# A7_FUNCTION2_-.net
KiCad netlist of a schematic drawn in Altium Designer
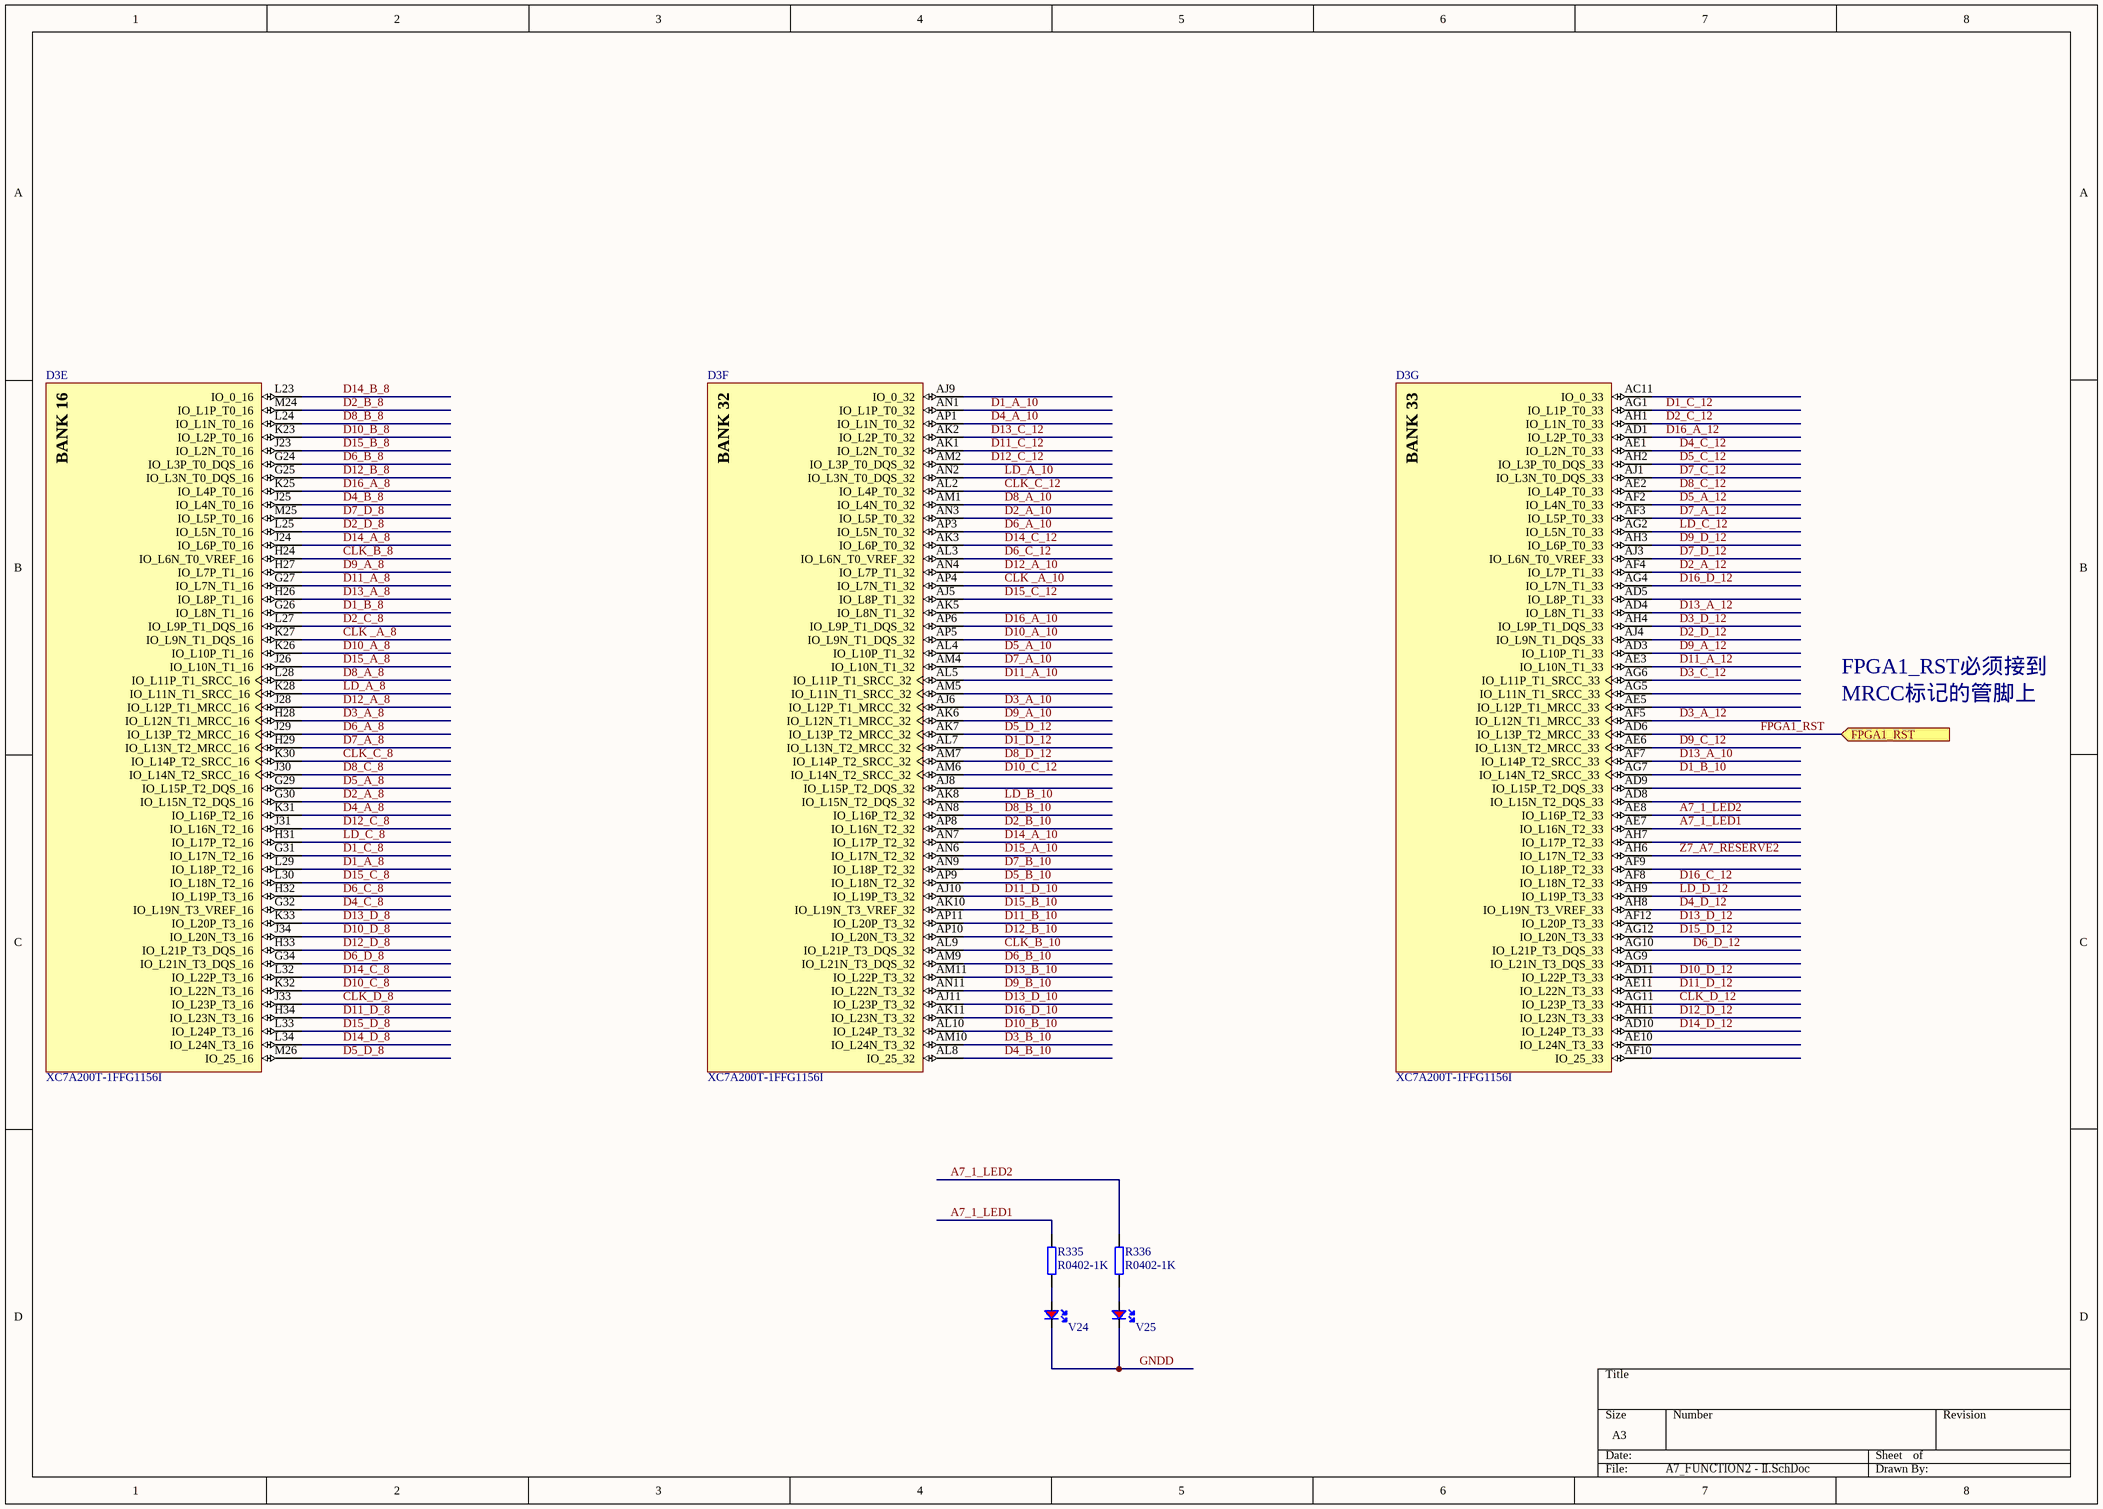
[diagram p0: A7_FUNCTION2 - Ⅱ.SchDoc]

(export (version "E")
  (design (tool "Eeschema 10.0.6"))
  (components
    (comp (ref "D3")
      (value "XC7A200T-1FFG1156I")
      (footprint "FFG1156")
      (description "Artix-7 FPGA, 500 User I/Os, 16 GTP, 1156-Ball BGA, Speed Grade 1, Industrial Grade, Pb-Free")
      (fields (field (name "GENERIC PART NUMBER") "XC7A200T") (field (name "MANUFACTURER") "Xilinx"))
      (libsource (lib "Xilinx Artix-7") (part "XC7A200T-1FFG1156I"))
    )
    (comp (ref "R335")
      (value "R0402-1K")
      (footprint "R0402")
      (fields (field (name "SCHEMATIC_PART") "RES") (field (name "MANUFACTURER") "SAMSUNG"))
      (libsource (lib "Database_Libs1") (part "RES"))
    )
    (comp (ref "R336")
      (value "R0402-1K")
      (footprint "R0402")
      (fields (field (name "SCHEMATIC_PART") "RES") (field (name "MANUFACTURER") "SAMSUNG"))
      (libsource (lib "Database_Libs1") (part "RES"))
    )
    (comp (ref "V24")
      (value "LED-R0603")
      (footprint "LED-R0603")
      (description "表贴发光二极管, 0603封装, 体积1.6x0.8mm, 红色, 高度0.8mm")
      (fields (field (name "SCHEMATIC_PART") "LED-R"))
      (libsource (lib "Database_Libs1") (part "LED-R"))
    )
    (comp (ref "V25")
      (value "LED-R0603")
      (footprint "LED-R0603")
      (description "表贴发光二极管, 0603封装, 体积1.6x0.8mm, 红色, 高度0.8mm")
      (fields (field (name "SCHEMATIC_PART") "LED-R"))
      (libsource (lib "Database_Libs1") (part "LED-R"))
    )
  )
  (nets
    (net (code "1") (name "/A7_1_LED1") (class "Default")
      (node (ref "D3") (pin "AE7") (pinfunction "IO_L16N_T2_33_AE7") (pintype "bidirectional"))
      (node (ref "R335") (pin "2") (pintype "passive"))
    )
    (net (code "2") (name "/A7_1_LED2") (class "Default")
      (node (ref "D3") (pin "AE8") (pinfunction "IO_L16P_T2_33_AE8") (pintype "bidirectional"))
      (node (ref "R336") (pin "2") (pintype "passive"))
    )
    (net (code "3") (name "/CLK _A_8") (class "Default")
      (node (ref "D3") (pin "K27") (pinfunction "IO_L9N_T1_DQS_16_K27") (pintype "bidirectional"))
    )
    (net (code "4") (name "/CLK _A_10") (class "Default")
      (node (ref "D3") (pin "AP4") (pinfunction "IO_L7N_T1_32_AP4") (pintype "bidirectional"))
    )
    (net (code "5") (name "/CLK_B_8") (class "Default")
      (node (ref "D3") (pin "H24") (pinfunction "IO_L6N_T0_VREF_16_H24") (pintype "bidirectional"))
    )
    (net (code "6") (name "/CLK_B_10") (class "Default")
      (node (ref "D3") (pin "AL9") (pinfunction "IO_L21P_T3_DQS_32_AL9") (pintype "bidirectional"))
    )
    (net (code "7") (name "/CLK_C_8") (class "Default")
      (node (ref "D3") (pin "K30") (pinfunction "IO_L14P_T2_SRCC_16_K30") (pintype "bidirectional"))
    )
    (net (code "8") (name "/CLK_C_12") (class "Default")
      (node (ref "D3") (pin "AL2") (pinfunction "IO_L4P_T0_32_AL2") (pintype "bidirectional"))
    )
    (net (code "9") (name "/CLK_D_8") (class "Default")
      (node (ref "D3") (pin "J33") (pinfunction "IO_L23P_T3_16_J33") (pintype "bidirectional"))
    )
    (net (code "10") (name "/CLK_D_12") (class "Default")
      (node (ref "D3") (pin "AG11") (pinfunction "IO_L23P_T3_33_AG11") (pintype "bidirectional"))
    )
    (net (code "11") (name "/D1_A_8") (class "Default")
      (node (ref "D3") (pin "L29") (pinfunction "IO_L18P_T2_16_L29") (pintype "bidirectional"))
    )
    (net (code "12") (name "/D1_A_10") (class "Default")
      (node (ref "D3") (pin "AN1") (pinfunction "IO_L1P_T0_32_AN1") (pintype "bidirectional"))
    )
    (net (code "13") (name "/D1_B_8") (class "Default")
      (node (ref "D3") (pin "G26") (pinfunction "IO_L8N_T1_16_G26") (pintype "bidirectional"))
    )
    (net (code "14") (name "/D1_B_10") (class "Default")
      (node (ref "D3") (pin "AG7") (pinfunction "IO_L14N_T2_SRCC_33_AG7") (pintype "bidirectional"))
    )
    (net (code "15") (name "/D1_C_8") (class "Default")
      (node (ref "D3") (pin "G31") (pinfunction "IO_L17N_T2_16_G31") (pintype "bidirectional"))
    )
    (net (code "16") (name "/D1_C_12") (class "Default")
      (node (ref "D3") (pin "AG1") (pinfunction "IO_L1P_T0_33_AG1") (pintype "bidirectional"))
    )
    (net (code "17") (name "/D1_D_12") (class "Default")
      (node (ref "D3") (pin "AL7") (pinfunction "IO_L13N_T2_MRCC_32_AL7") (pintype "bidirectional"))
    )
    (net (code "18") (name "/D2_A_8") (class "Default")
      (node (ref "D3") (pin "G30") (pinfunction "IO_L15N_T2_DQS_16_G30") (pintype "bidirectional"))
    )
    (net (code "19") (name "/D2_A_10") (class "Default")
      (node (ref "D3") (pin "AN3") (pinfunction "IO_L5P_T0_32_AN3") (pintype "bidirectional"))
    )
    (net (code "20") (name "/D2_A_12") (class "Default")
      (node (ref "D3") (pin "AF4") (pinfunction "IO_L7P_T1_33_AF4") (pintype "bidirectional"))
    )
    (net (code "21") (name "/D2_B_8") (class "Default")
      (node (ref "D3") (pin "M24") (pinfunction "IO_L1P_T0_16_M24") (pintype "bidirectional"))
    )
    (net (code "22") (name "/D2_B_10") (class "Default")
      (node (ref "D3") (pin "AP8") (pinfunction "IO_L16N_T2_32_AP8") (pintype "bidirectional"))
    )
    (net (code "23") (name "/D2_C_8") (class "Default")
      (node (ref "D3") (pin "L27") (pinfunction "IO_L9P_T1_DQS_16_L27") (pintype "bidirectional"))
    )
    (net (code "24") (name "/D2_C_12") (class "Default")
      (node (ref "D3") (pin "AH1") (pinfunction "IO_L1N_T0_33_AH1") (pintype "bidirectional"))
    )
    (net (code "25") (name "/D2_D_8") (class "Default")
      (node (ref "D3") (pin "L25") (pinfunction "IO_L5N_T0_16_L25") (pintype "bidirectional"))
    )
    (net (code "26") (name "/D2_D_12") (class "Default")
      (node (ref "D3") (pin "AJ4") (pinfunction "IO_L9N_T1_DQS_33_AJ4") (pintype "bidirectional"))
    )
    (net (code "27") (name "/D3_A_8") (class "Default")
      (node (ref "D3") (pin "H28") (pinfunction "IO_L12N_T1_MRCC_16_H28") (pintype "bidirectional"))
    )
    (net (code "28") (name "/D3_A_10") (class "Default")
      (node (ref "D3") (pin "AJ6") (pinfunction "IO_L12P_T1_MRCC_32_AJ6") (pintype "bidirectional"))
    )
    (net (code "29") (name "/D3_A_12") (class "Default")
      (node (ref "D3") (pin "AF5") (pinfunction "IO_L12N_T1_MRCC_33_AF5") (pintype "bidirectional"))
    )
    (net (code "30") (name "/D3_B_10") (class "Default")
      (node (ref "D3") (pin "AM10") (pinfunction "IO_L24N_T3_32_AM10") (pintype "bidirectional"))
    )
    (net (code "31") (name "/D3_C_12") (class "Default")
      (node (ref "D3") (pin "AG6") (pinfunction "IO_L11P_T1_SRCC_33_AG6") (pintype "bidirectional"))
    )
    (net (code "32") (name "/D3_D_12") (class "Default")
      (node (ref "D3") (pin "AH4") (pinfunction "IO_L9P_T1_DQS_33_AH4") (pintype "bidirectional"))
    )
    (net (code "33") (name "/D4_A_8") (class "Default")
      (node (ref "D3") (pin "K31") (pinfunction "IO_L16P_T2_16_K31") (pintype "bidirectional"))
    )
    (net (code "34") (name "/D4_A_10") (class "Default")
      (node (ref "D3") (pin "AP1") (pinfunction "IO_L1N_T0_32_AP1") (pintype "bidirectional"))
    )
    (net (code "35") (name "/D4_B_8") (class "Default")
      (node (ref "D3") (pin "J25") (pinfunction "IO_L4N_T0_16_J25") (pintype "bidirectional"))
    )
    (net (code "36") (name "/D4_B_10") (class "Default")
      (node (ref "D3") (pin "AL8") (pinfunction "IO_25_32_AL8") (pintype "bidirectional"))
    )
    (net (code "37") (name "/D4_C_8") (class "Default")
      (node (ref "D3") (pin "G32") (pinfunction "IO_L19N_T3_VREF_16_G32") (pintype "bidirectional"))
    )
    (net (code "38") (name "/D4_C_12") (class "Default")
      (node (ref "D3") (pin "AE1") (pinfunction "IO_L2N_T0_33_AE1") (pintype "bidirectional"))
    )
    (net (code "39") (name "/D4_D_12") (class "Default")
      (node (ref "D3") (pin "AH8") (pinfunction "IO_L19N_T3_VREF_33_AH8") (pintype "bidirectional"))
    )
    (net (code "40") (name "/D5_A_8") (class "Default")
      (node (ref "D3") (pin "G29") (pinfunction "IO_L15P_T2_DQS_16_G29") (pintype "bidirectional"))
    )
    (net (code "41") (name "/D5_A_10") (class "Default")
      (node (ref "D3") (pin "AL4") (pinfunction "IO_L10P_T1_32_AL4") (pintype "bidirectional"))
    )
    (net (code "42") (name "/D5_A_12") (class "Default")
      (node (ref "D3") (pin "AF2") (pinfunction "IO_L4N_T0_33_AF2") (pintype "bidirectional"))
    )
    (net (code "43") (name "/D5_B_10") (class "Default")
      (node (ref "D3") (pin "AP9") (pinfunction "IO_L18N_T2_32_AP9") (pintype "bidirectional"))
    )
    (net (code "44") (name "/D5_C_12") (class "Default")
      (node (ref "D3") (pin "AH2") (pinfunction "IO_L3P_T0_DQS_33_AH2") (pintype "bidirectional"))
    )
    (net (code "45") (name "/D5_D_8") (class "Default")
      (node (ref "D3") (pin "M26") (pinfunction "IO_25_16_M26") (pintype "bidirectional"))
    )
    (net (code "46") (name "/D5_D_12") (class "Default")
      (node (ref "D3") (pin "AK7") (pinfunction "IO_L13P_T2_MRCC_32_AK7") (pintype "bidirectional"))
    )
    (net (code "47") (name "/D6_A_8") (class "Default")
      (node (ref "D3") (pin "J29") (pinfunction "IO_L13P_T2_MRCC_16_J29") (pintype "bidirectional"))
    )
    (net (code "48") (name "/D6_A_10") (class "Default")
      (node (ref "D3") (pin "AP3") (pinfunction "IO_L5N_T0_32_AP3") (pintype "bidirectional"))
    )
    (net (code "49") (name "/D6_B_8") (class "Default")
      (node (ref "D3") (pin "G24") (pinfunction "IO_L3P_T0_DQS_16_G24") (pintype "bidirectional"))
    )
    (net (code "50") (name "/D6_B_10") (class "Default")
      (node (ref "D3") (pin "AM9") (pinfunction "IO_L21N_T3_DQS_32_AM9") (pintype "bidirectional"))
    )
    (net (code "51") (name "/D6_C_8") (class "Default")
      (node (ref "D3") (pin "H32") (pinfunction "IO_L19P_T3_16_H32") (pintype "bidirectional"))
    )
    (net (code "52") (name "/D6_C_12") (class "Default")
      (node (ref "D3") (pin "AL3") (pinfunction "IO_L6N_T0_VREF_32_AL3") (pintype "bidirectional"))
    )
    (net (code "53") (name "/D6_D_8") (class "Default")
      (node (ref "D3") (pin "G34") (pinfunction "IO_L21N_T3_DQS_16_G34") (pintype "bidirectional"))
    )
    (net (code "54") (name "/D6_D_12") (class "Default")
      (node (ref "D3") (pin "AG10") (pinfunction "IO_L21P_T3_DQS_33_AG10") (pintype "bidirectional"))
    )
    (net (code "55") (name "/D7_A_8") (class "Default")
      (node (ref "D3") (pin "H29") (pinfunction "IO_L13N_T2_MRCC_16_H29") (pintype "bidirectional"))
    )
    (net (code "56") (name "/D7_A_10") (class "Default")
      (node (ref "D3") (pin "AM4") (pinfunction "IO_L10N_T1_32_AM4") (pintype "bidirectional"))
    )
    (net (code "57") (name "/D7_A_12") (class "Default")
      (node (ref "D3") (pin "AF3") (pinfunction "IO_L5P_T0_33_AF3") (pintype "bidirectional"))
    )
    (net (code "58") (name "/D7_B_10") (class "Default")
      (node (ref "D3") (pin "AN9") (pinfunction "IO_L18P_T2_32_AN9") (pintype "bidirectional"))
    )
    (net (code "59") (name "/D7_C_12") (class "Default")
      (node (ref "D3") (pin "AJ1") (pinfunction "IO_L3N_T0_DQS_33_AJ1") (pintype "bidirectional"))
    )
    (net (code "60") (name "/D7_D_8") (class "Default")
      (node (ref "D3") (pin "M25") (pinfunction "IO_L5P_T0_16_M25") (pintype "bidirectional"))
    )
    (net (code "61") (name "/D7_D_12") (class "Default")
      (node (ref "D3") (pin "AJ3") (pinfunction "IO_L6N_T0_VREF_33_AJ3") (pintype "bidirectional"))
    )
    (net (code "62") (name "/D8_A_8") (class "Default")
      (node (ref "D3") (pin "L28") (pinfunction "IO_L11P_T1_SRCC_16_L28") (pintype "bidirectional"))
    )
    (net (code "63") (name "/D8_A_10") (class "Default")
      (node (ref "D3") (pin "AM1") (pinfunction "IO_L4N_T0_32_AM1") (pintype "bidirectional"))
    )
    (net (code "64") (name "/D8_B_8") (class "Default")
      (node (ref "D3") (pin "L24") (pinfunction "IO_L1N_T0_16_L24") (pintype "bidirectional"))
    )
    (net (code "65") (name "/D8_B_10") (class "Default")
      (node (ref "D3") (pin "AN8") (pinfunction "IO_L16P_T2_32_AN8") (pintype "bidirectional"))
    )
    (net (code "66") (name "/D8_C_8") (class "Default")
      (node (ref "D3") (pin "J30") (pinfunction "IO_L14N_T2_SRCC_16_J30") (pintype "bidirectional"))
    )
    (net (code "67") (name "/D8_C_12") (class "Default")
      (node (ref "D3") (pin "AE2") (pinfunction "IO_L4P_T0_33_AE2") (pintype "bidirectional"))
    )
    (net (code "68") (name "/D8_D_12") (class "Default")
      (node (ref "D3") (pin "AM7") (pinfunction "IO_L14P_T2_SRCC_32_AM7") (pintype "bidirectional"))
    )
    (net (code "69") (name "/D9_A_8") (class "Default")
      (node (ref "D3") (pin "H27") (pinfunction "IO_L7P_T1_16_H27") (pintype "bidirectional"))
    )
    (net (code "70") (name "/D9_A_10") (class "Default")
      (node (ref "D3") (pin "AK6") (pinfunction "IO_L12N_T1_MRCC_32_AK6") (pintype "bidirectional"))
    )
    (net (code "71") (name "/D9_A_12") (class "Default")
      (node (ref "D3") (pin "AD3") (pinfunction "IO_L10P_T1_33_AD3") (pintype "bidirectional"))
    )
    (net (code "72") (name "/D9_B_10") (class "Default")
      (node (ref "D3") (pin "AN11") (pinfunction "IO_L22N_T3_32_AN11") (pintype "bidirectional"))
    )
    (net (code "73") (name "/D9_C_12") (class "Default")
      (node (ref "D3") (pin "AE6") (pinfunction "IO_L13N_T2_MRCC_33_AE6") (pintype "bidirectional"))
    )
    (net (code "74") (name "/D9_D_12") (class "Default")
      (node (ref "D3") (pin "AH3") (pinfunction "IO_L6P_T0_33_AH3") (pintype "bidirectional"))
    )
    (net (code "75") (name "/D10_A_8") (class "Default")
      (node (ref "D3") (pin "K26") (pinfunction "IO_L10P_T1_16_K26") (pintype "bidirectional"))
    )
    (net (code "76") (name "/D10_A_10") (class "Default")
      (node (ref "D3") (pin "AP5") (pinfunction "IO_L9N_T1_DQS_32_AP5") (pintype "bidirectional"))
    )
    (net (code "77") (name "/D10_B_8") (class "Default")
      (node (ref "D3") (pin "K23") (pinfunction "IO_L2P_T0_16_K23") (pintype "bidirectional"))
    )
    (net (code "78") (name "/D10_B_10") (class "Default")
      (node (ref "D3") (pin "AL10") (pinfunction "IO_L24P_T3_32_AL10") (pintype "bidirectional"))
    )
    (net (code "79") (name "/D10_C_8") (class "Default")
      (node (ref "D3") (pin "K32") (pinfunction "IO_L22N_T3_16_K32") (pintype "bidirectional"))
    )
    (net (code "80") (name "/D10_C_12") (class "Default")
      (node (ref "D3") (pin "AM6") (pinfunction "IO_L14N_T2_SRCC_32_AM6") (pintype "bidirectional"))
    )
    (net (code "81") (name "/D10_D_8") (class "Default")
      (node (ref "D3") (pin "J34") (pinfunction "IO_L20N_T3_16_J34") (pintype "bidirectional"))
    )
    (net (code "82") (name "/D10_D_12") (class "Default")
      (node (ref "D3") (pin "AD11") (pinfunction "IO_L22P_T3_33_AD11") (pintype "bidirectional"))
    )
    (net (code "83") (name "/D11_A_8") (class "Default")
      (node (ref "D3") (pin "G27") (pinfunction "IO_L7N_T1_16_G27") (pintype "bidirectional"))
    )
    (net (code "84") (name "/D11_A_10") (class "Default")
      (node (ref "D3") (pin "AL5") (pinfunction "IO_L11P_T1_SRCC_32_AL5") (pintype "bidirectional"))
    )
    (net (code "85") (name "/D11_A_12") (class "Default")
      (node (ref "D3") (pin "AE3") (pinfunction "IO_L10N_T1_33_AE3") (pintype "bidirectional"))
    )
    (net (code "86") (name "/D11_B_10") (class "Default")
      (node (ref "D3") (pin "AP11") (pinfunction "IO_L20P_T3_32_AP11") (pintype "bidirectional"))
    )
    (net (code "87") (name "/D11_C_12") (class "Default")
      (node (ref "D3") (pin "AK1") (pinfunction "IO_L2N_T0_32_AK1") (pintype "bidirectional"))
    )
    (net (code "88") (name "/D11_D_8") (class "Default")
      (node (ref "D3") (pin "H34") (pinfunction "IO_L23N_T3_16_H34") (pintype "bidirectional"))
    )
    (net (code "89") (name "/D11_D_10") (class "Default")
      (node (ref "D3") (pin "AJ10") (pinfunction "IO_L19P_T3_32_AJ10") (pintype "bidirectional"))
    )
    (net (code "90") (name "/D11_D_12") (class "Default")
      (node (ref "D3") (pin "AE11") (pinfunction "IO_L22N_T3_33_AE11") (pintype "bidirectional"))
    )
    (net (code "91") (name "/D12_A_8") (class "Default")
      (node (ref "D3") (pin "J28") (pinfunction "IO_L12P_T1_MRCC_16_J28") (pintype "bidirectional"))
    )
    (net (code "92") (name "/D12_A_10") (class "Default")
      (node (ref "D3") (pin "AN4") (pinfunction "IO_L7P_T1_32_AN4") (pintype "bidirectional"))
    )
    (net (code "93") (name "/D12_B_8") (class "Default")
      (node (ref "D3") (pin "G25") (pinfunction "IO_L3N_T0_DQS_16_G25") (pintype "bidirectional"))
    )
    (net (code "94") (name "/D12_B_10") (class "Default")
      (node (ref "D3") (pin "AP10") (pinfunction "IO_L20N_T3_32_AP10") (pintype "bidirectional"))
    )
    (net (code "95") (name "/D12_C_8") (class "Default")
      (node (ref "D3") (pin "J31") (pinfunction "IO_L16N_T2_16_J31") (pintype "bidirectional"))
    )
    (net (code "96") (name "/D12_C_12") (class "Default")
      (node (ref "D3") (pin "AM2") (pinfunction "IO_L3P_T0_DQS_32_AM2") (pintype "bidirectional"))
    )
    (net (code "97") (name "/D12_D_8") (class "Default")
      (node (ref "D3") (pin "H33") (pinfunction "IO_L21P_T3_DQS_16_H33") (pintype "bidirectional"))
    )
    (net (code "98") (name "/D12_D_12") (class "Default")
      (node (ref "D3") (pin "AH11") (pinfunction "IO_L23N_T3_33_AH11") (pintype "bidirectional"))
    )
    (net (code "99") (name "/D13_A_8") (class "Default")
      (node (ref "D3") (pin "H26") (pinfunction "IO_L8P_T1_16_H26") (pintype "bidirectional"))
    )
    (net (code "100") (name "/D13_A_10") (class "Default")
      (node (ref "D3") (pin "AF7") (pinfunction "IO_L14P_T2_SRCC_33_AF7") (pintype "bidirectional"))
    )
    (net (code "101") (name "/D13_A_12") (class "Default")
      (node (ref "D3") (pin "AD4") (pinfunction "IO_L8N_T1_33_AD4") (pintype "bidirectional"))
    )
    (net (code "102") (name "/D13_B_10") (class "Default")
      (node (ref "D3") (pin "AM11") (pinfunction "IO_L22P_T3_32_AM11") (pintype "bidirectional"))
    )
    (net (code "103") (name "/D13_C_12") (class "Default")
      (node (ref "D3") (pin "AK2") (pinfunction "IO_L2P_T0_32_AK2") (pintype "bidirectional"))
    )
    (net (code "104") (name "/D13_D_8") (class "Default")
      (node (ref "D3") (pin "K33") (pinfunction "IO_L20P_T3_16_K33") (pintype "bidirectional"))
    )
    (net (code "105") (name "/D13_D_10") (class "Default")
      (node (ref "D3") (pin "AJ11") (pinfunction "IO_L23P_T3_32_AJ11") (pintype "bidirectional"))
    )
    (net (code "106") (name "/D13_D_12") (class "Default")
      (node (ref "D3") (pin "AF12") (pinfunction "IO_L20P_T3_33_AF12") (pintype "bidirectional"))
    )
    (net (code "107") (name "/D14_A_8") (class "Default")
      (node (ref "D3") (pin "J24") (pinfunction "IO_L6P_T0_16_J24") (pintype "bidirectional"))
    )
    (net (code "108") (name "/D14_A_10") (class "Default")
      (node (ref "D3") (pin "AN7") (pinfunction "IO_L17P_T2_32_AN7") (pintype "bidirectional"))
    )
    (net (code "109") (name "/D14_B_8") (class "Default")
      (node (ref "D3") (pin "L23") (pinfunction "IO_0_16_L23") (pintype "bidirectional"))
    )
    (net (code "110") (name "/D14_C_8") (class "Default")
      (node (ref "D3") (pin "L32") (pinfunction "IO_L22P_T3_16_L32") (pintype "bidirectional"))
    )
    (net (code "111") (name "/D14_C_12") (class "Default")
      (node (ref "D3") (pin "AK3") (pinfunction "IO_L6P_T0_32_AK3") (pintype "bidirectional"))
    )
    (net (code "112") (name "/D14_D_8") (class "Default")
      (node (ref "D3") (pin "L34") (pinfunction "IO_L24N_T3_16_L34") (pintype "bidirectional"))
    )
    (net (code "113") (name "/D14_D_12") (class "Default")
      (node (ref "D3") (pin "AD10") (pinfunction "IO_L24P_T3_33_AD10") (pintype "bidirectional"))
    )
    (net (code "114") (name "/D15_A_8") (class "Default")
      (node (ref "D3") (pin "J26") (pinfunction "IO_L10N_T1_16_J26") (pintype "bidirectional"))
    )
    (net (code "115") (name "/D15_A_10") (class "Default")
      (node (ref "D3") (pin "AN6") (pinfunction "IO_L17N_T2_32_AN6") (pintype "bidirectional"))
    )
    (net (code "116") (name "/D15_B_8") (class "Default")
      (node (ref "D3") (pin "J23") (pinfunction "IO_L2N_T0_16_J23") (pintype "bidirectional"))
    )
    (net (code "117") (name "/D15_B_10") (class "Default")
      (node (ref "D3") (pin "AK10") (pinfunction "IO_L19N_T3_VREF_32_AK10") (pintype "bidirectional"))
    )
    (net (code "118") (name "/D15_C_8") (class "Default")
      (node (ref "D3") (pin "L30") (pinfunction "IO_L18N_T2_16_L30") (pintype "bidirectional"))
    )
    (net (code "119") (name "/D15_C_12") (class "Default")
      (node (ref "D3") (pin "AJ5") (pinfunction "IO_L8P_T1_32_AJ5") (pintype "bidirectional"))
    )
    (net (code "120") (name "/D15_D_8") (class "Default")
      (node (ref "D3") (pin "L33") (pinfunction "IO_L24P_T3_16_L33") (pintype "bidirectional"))
    )
    (net (code "121") (name "/D15_D_12") (class "Default")
      (node (ref "D3") (pin "AG12") (pinfunction "IO_L20N_T3_33_AG12") (pintype "bidirectional"))
    )
    (net (code "122") (name "/D16_A_8") (class "Default")
      (node (ref "D3") (pin "K25") (pinfunction "IO_L4P_T0_16_K25") (pintype "bidirectional"))
    )
    (net (code "123") (name "/D16_A_10") (class "Default")
      (node (ref "D3") (pin "AP6") (pinfunction "IO_L9P_T1_DQS_32_AP6") (pintype "bidirectional"))
    )
    (net (code "124") (name "/D16_A_12") (class "Default")
      (node (ref "D3") (pin "AD1") (pinfunction "IO_L2P_T0_33_AD1") (pintype "bidirectional"))
    )
    (net (code "125") (name "/D16_C_12") (class "Default")
      (node (ref "D3") (pin "AF8") (pinfunction "IO_L18N_T2_33_AF8") (pintype "bidirectional"))
    )
    (net (code "126") (name "/D16_D_10") (class "Default")
      (node (ref "D3") (pin "AK11") (pinfunction "IO_L23N_T3_32_AK11") (pintype "bidirectional"))
    )
    (net (code "127") (name "/D16_D_12") (class "Default")
      (node (ref "D3") (pin "AG4") (pinfunction "IO_L7N_T1_33_AG4") (pintype "bidirectional"))
    )
    (net (code "128") (name "/FPGA1_RST") (class "Default")
      (node (ref "D3") (pin "AD6") (pinfunction "IO_L13P_T2_MRCC_33_AD6") (pintype "bidirectional"))
    )
    (net (code "129") (name "/GNDD") (class "Default")
      (node (ref "V24") (pin "2") (pinfunction "K_2") (pintype "passive"))
      (node (ref "V25") (pin "2") (pinfunction "K_2") (pintype "passive"))
    )
    (net (code "130") (name "/LD_A_8") (class "Default")
      (node (ref "D3") (pin "K28") (pinfunction "IO_L11N_T1_SRCC_16_K28") (pintype "bidirectional"))
    )
    (net (code "131") (name "/LD_A_10") (class "Default")
      (node (ref "D3") (pin "AN2") (pinfunction "IO_L3N_T0_DQS_32_AN2") (pintype "bidirectional"))
    )
    (net (code "132") (name "/LD_B_10") (class "Default")
      (node (ref "D3") (pin "AK8") (pinfunction "IO_L15N_T2_DQS_32_AK8") (pintype "bidirectional"))
    )
    (net (code "133") (name "/LD_C_8") (class "Default")
      (node (ref "D3") (pin "H31") (pinfunction "IO_L17P_T2_16_H31") (pintype "bidirectional"))
    )
    (net (code "134") (name "/LD_C_12") (class "Default")
      (node (ref "D3") (pin "AG2") (pinfunction "IO_L5N_T0_33_AG2") (pintype "bidirectional"))
    )
    (net (code "135") (name "/LD_D_12") (class "Default")
      (node (ref "D3") (pin "AH9") (pinfunction "IO_L19P_T3_33_AH9") (pintype "bidirectional"))
    )
    (net (code "136") (name "/Z7_A7_RESERVE2") (class "Default")
      (node (ref "D3") (pin "AH6") (pinfunction "IO_L17N_T2_33_AH6") (pintype "bidirectional"))
    )
    (net (code "137") (name "Net-(V24-A)") (class "Default")
      (node (ref "R335") (pin "1") (pintype "passive"))
      (node (ref "V24") (pin "1") (pinfunction "A_1") (pintype "passive"))
    )
    (net (code "138") (name "Net-(V25-A)") (class "Default")
      (node (ref "R336") (pin "1") (pintype "passive"))
      (node (ref "V25") (pin "1") (pinfunction "A_1") (pintype "passive"))
    )
    (net (code "139") (name "unconnected-(D3F-IO_0_32-PadAJ9)") (class "Default")
      (node (ref "D3") (pin "AJ9") (pinfunction "IO_0_32_AJ9") (pintype "bidirectional"))
    )
    (net (code "140") (name "unconnected-(D3F-IO_L8N_T1_32-PadAK5)") (class "Default")
      (node (ref "D3") (pin "AK5") (pinfunction "IO_L8N_T1_32_AK5") (pintype "bidirectional"))
    )
    (net (code "141") (name "unconnected-(D3F-IO_L11N_T1_SRCC_32-PadAM5)") (class "Default")
      (node (ref "D3") (pin "AM5") (pinfunction "IO_L11N_T1_SRCC_32_AM5") (pintype "bidirectional"))
    )
    (net (code "142") (name "unconnected-(D3F-IO_L15P_T2_DQS_32-PadAJ8)") (class "Default")
      (node (ref "D3") (pin "AJ8") (pinfunction "IO_L15P_T2_DQS_32_AJ8") (pintype "bidirectional"))
    )
    (net (code "143") (name "unconnected-(D3G-IO_0_33-PadAC11)") (class "Default")
      (node (ref "D3") (pin "AC11") (pinfunction "IO_0_33_AC11") (pintype "bidirectional"))
    )
    (net (code "144") (name "unconnected-(D3G-IO_25_33-PadAF10)") (class "Default")
      (node (ref "D3") (pin "AF10") (pinfunction "IO_25_33_AF10") (pintype "bidirectional"))
    )
    (net (code "145") (name "unconnected-(D3G-IO_L8P_T1_33-PadAD5)") (class "Default")
      (node (ref "D3") (pin "AD5") (pinfunction "IO_L8P_T1_33_AD5") (pintype "bidirectional"))
    )
    (net (code "146") (name "unconnected-(D3G-IO_L11N_T1_SRCC_33-PadAG5)") (class "Default")
      (node (ref "D3") (pin "AG5") (pinfunction "IO_L11N_T1_SRCC_33_AG5") (pintype "bidirectional"))
    )
    (net (code "147") (name "unconnected-(D3G-IO_L12P_T1_MRCC_33-PadAE5)") (class "Default")
      (node (ref "D3") (pin "AE5") (pinfunction "IO_L12P_T1_MRCC_33_AE5") (pintype "bidirectional"))
    )
    (net (code "148") (name "unconnected-(D3G-IO_L15N_T2_DQS_33-PadAD8)") (class "Default")
      (node (ref "D3") (pin "AD8") (pinfunction "IO_L15N_T2_DQS_33_AD8") (pintype "bidirectional"))
    )
    (net (code "149") (name "unconnected-(D3G-IO_L15P_T2_DQS_33-PadAD9)") (class "Default")
      (node (ref "D3") (pin "AD9") (pinfunction "IO_L15P_T2_DQS_33_AD9") (pintype "bidirectional"))
    )
    (net (code "150") (name "unconnected-(D3G-IO_L17P_T2_33-PadAH7)") (class "Default")
      (node (ref "D3") (pin "AH7") (pinfunction "IO_L17P_T2_33_AH7") (pintype "bidirectional"))
    )
    (net (code "151") (name "unconnected-(D3G-IO_L18P_T2_33-PadAF9)") (class "Default")
      (node (ref "D3") (pin "AF9") (pinfunction "IO_L18P_T2_33_AF9") (pintype "bidirectional"))
    )
    (net (code "152") (name "unconnected-(D3G-IO_L21N_T3_DQS_33-PadAG9)") (class "Default")
      (node (ref "D3") (pin "AG9") (pinfunction "IO_L21N_T3_DQS_33_AG9") (pintype "bidirectional"))
    )
    (net (code "153") (name "unconnected-(D3G-IO_L24N_T3_33-PadAE10)") (class "Default")
      (node (ref "D3") (pin "AE10") (pinfunction "IO_L24N_T3_33_AE10") (pintype "bidirectional"))
    )
  )
)
